# SwitchEthernet_-_Rev_A4.net
KiCad netlist of a schematic drawn in EAGLE
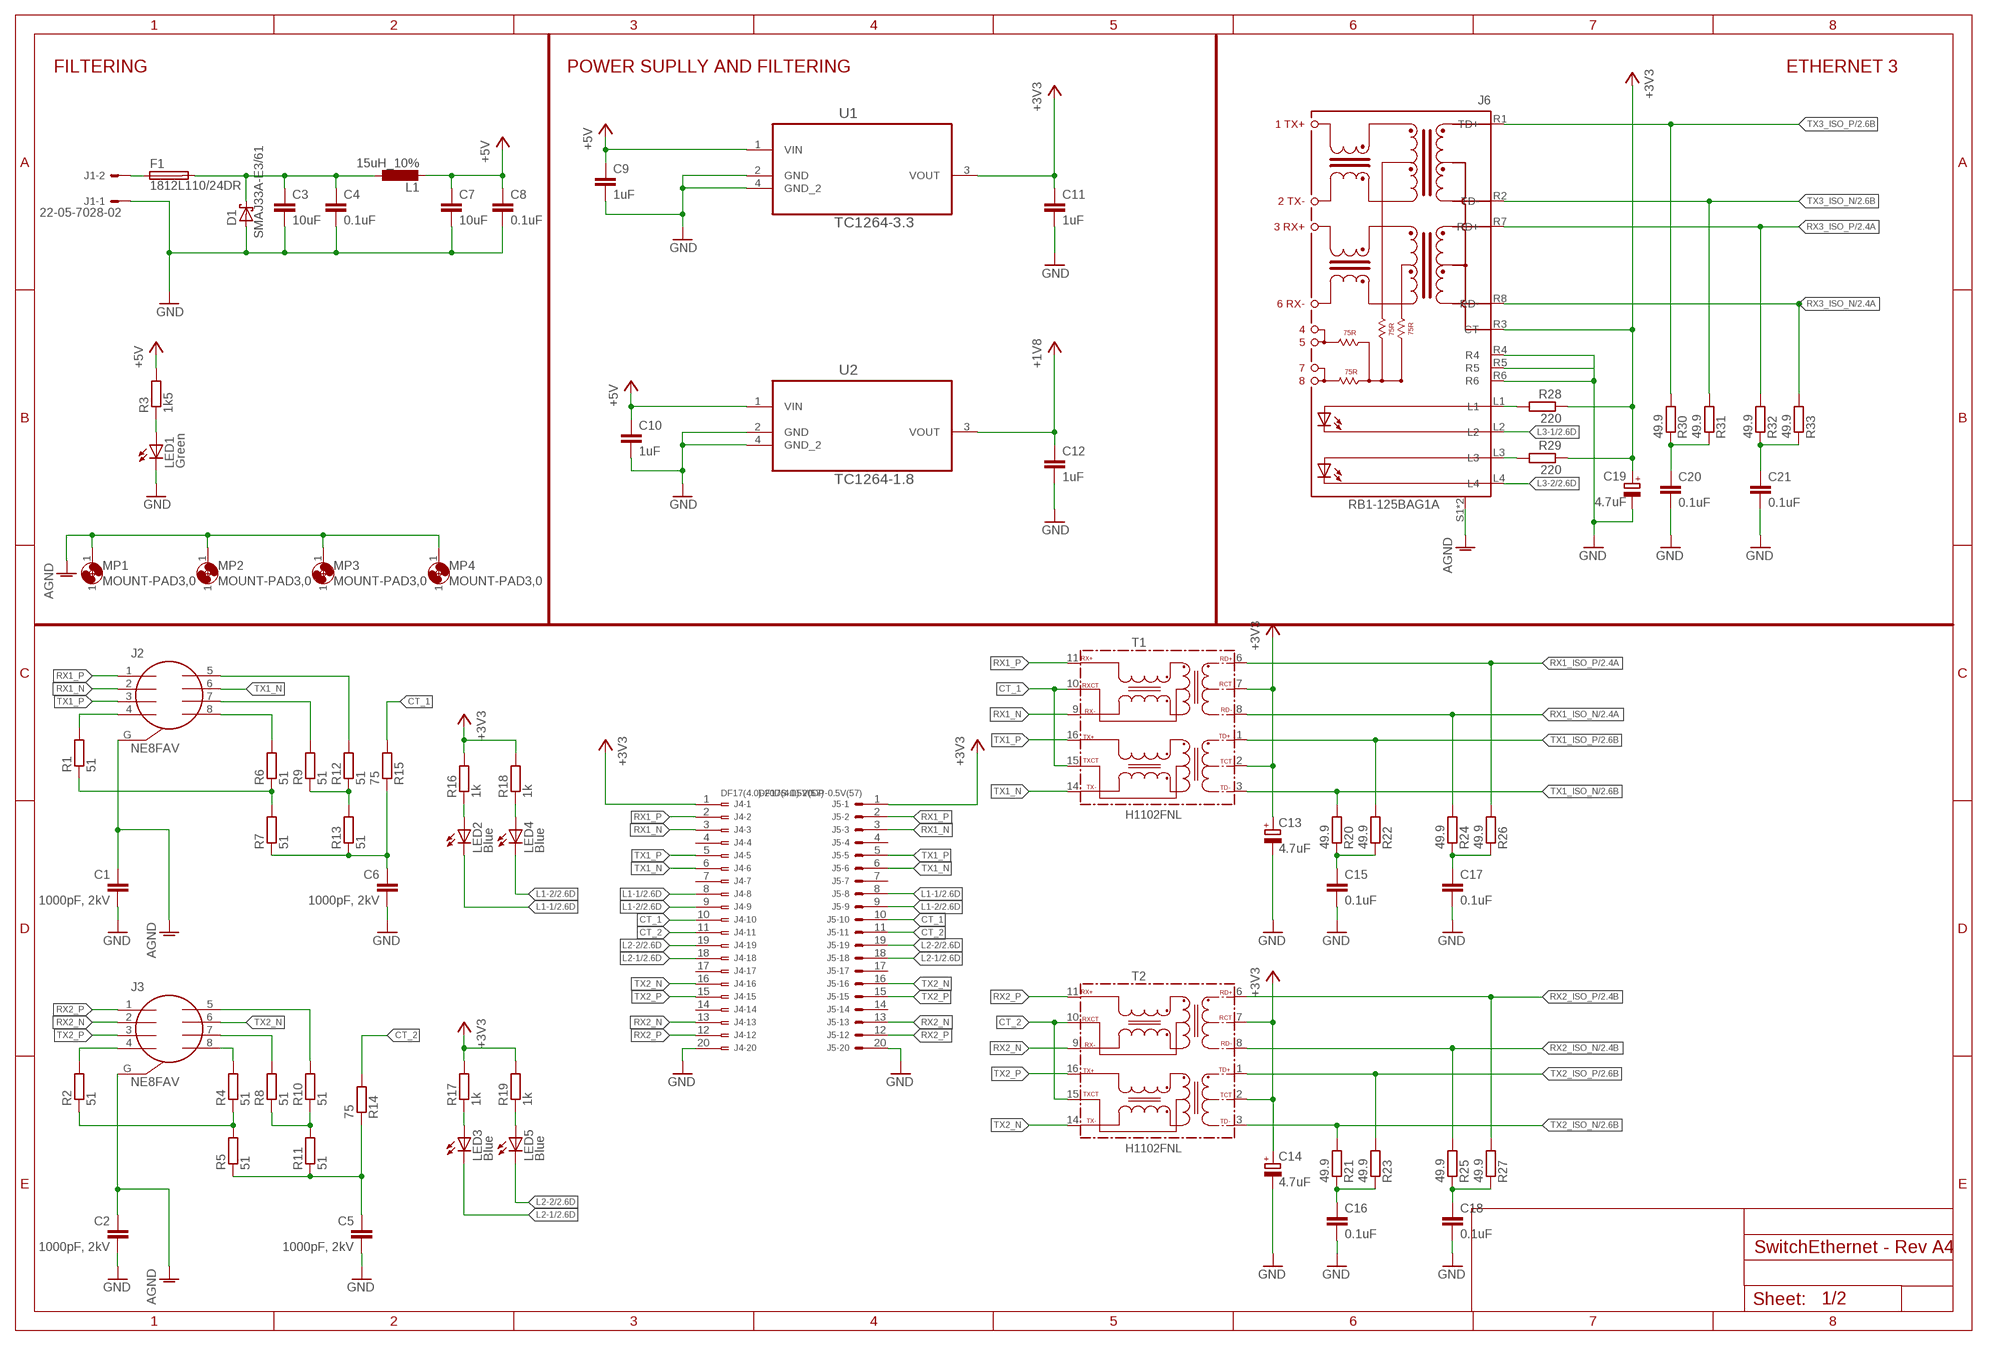
[diagram p0: schematic, sheet 1]
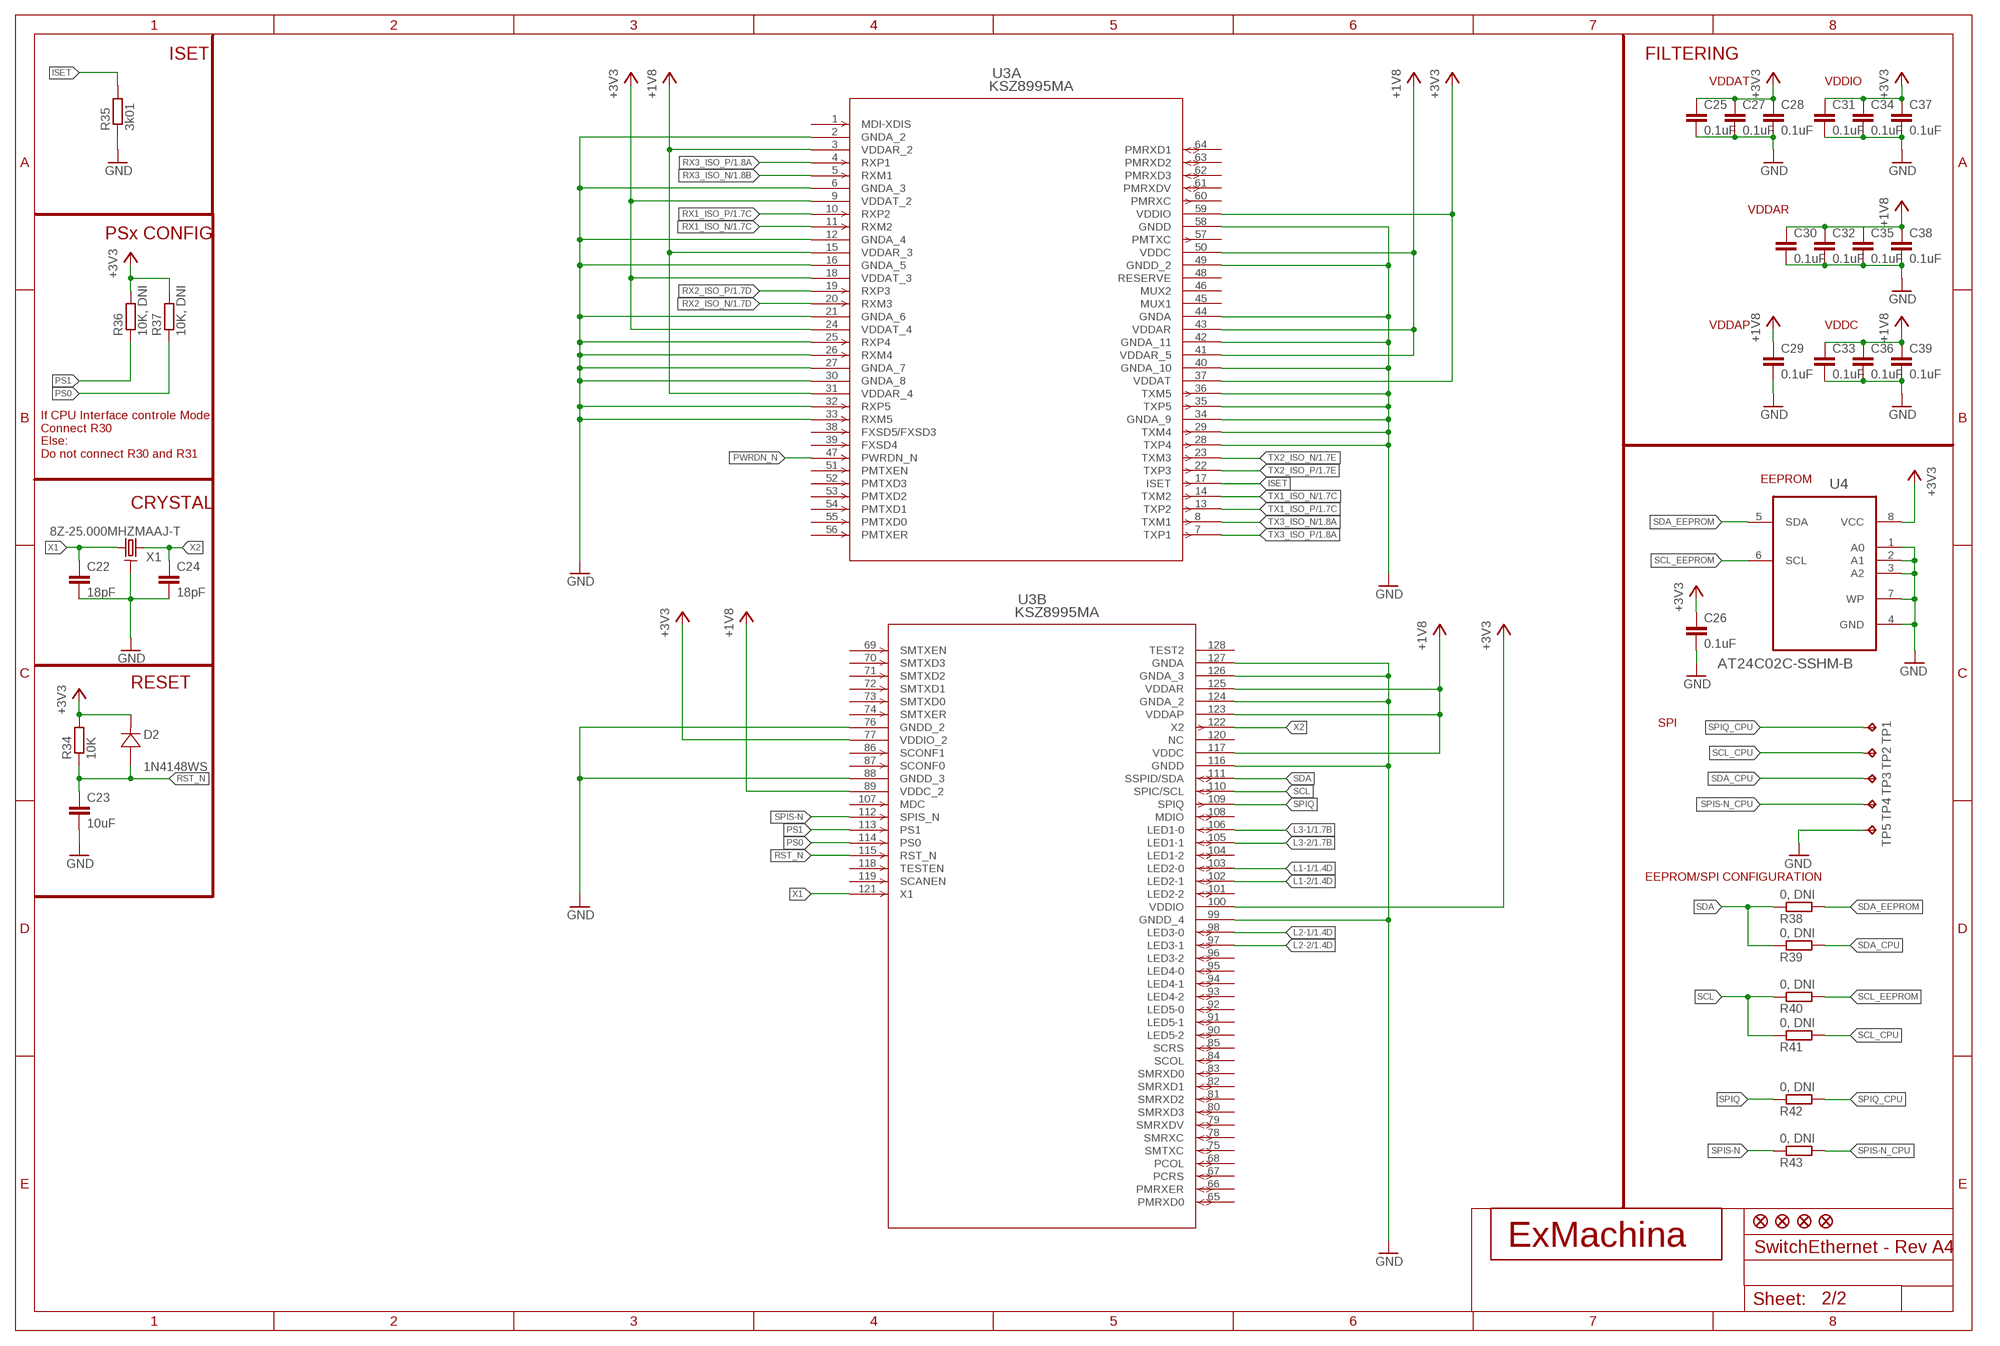
[diagram p1: schematic, sheet 2]

(export (version "E")
  (design (tool "Eeschema 10.0.6"))
  (components
    (comp (ref "C1")
      (value "1000pF, 2kV")
      (footprint "eagle-import:C1206")
      (fields (field (name "MPN") "MC1206B102K202CT"))
      (libsource (lib "eagle-import") (part "C-EUC1206"))
    )
    (comp (ref "C2")
      (value "1000pF, 2kV")
      (footprint "eagle-import:C1206")
      (fields (field (name "MPN") "MC1206B102K202CT"))
      (libsource (lib "eagle-import") (part "C-EUC1206"))
    )
    (comp (ref "C3")
      (value "10uF")
      (footprint "eagle-import:C0603")
      (fields (field (name "MPN") "GRM188R60J106ME47D"))
      (libsource (lib "eagle-import") (part "C-EUC0603"))
    )
    (comp (ref "C4")
      (value "0.1uF")
      (footprint "eagle-import:C0603")
      (fields (field (name "MPN") "MC0603B104K160CT"))
      (libsource (lib "eagle-import") (part "C-EUC0603"))
    )
    (comp (ref "C5")
      (value "1000pF, 2kV")
      (footprint "eagle-import:C1206")
      (fields (field (name "MPN") "MC1206B102K202CT"))
      (libsource (lib "eagle-import") (part "C-EUC1206"))
    )
    (comp (ref "C6")
      (value "1000pF, 2kV")
      (footprint "eagle-import:C1206")
      (fields (field (name "MPN") "MC1206B102K202CT"))
      (libsource (lib "eagle-import") (part "C-EUC1206"))
    )
    (comp (ref "C7")
      (value "10uF")
      (footprint "eagle-import:C0603")
      (fields (field (name "MPN") "GRM188R60J106ME47D"))
      (libsource (lib "eagle-import") (part "C-EUC0603"))
    )
    (comp (ref "C8")
      (value "0.1uF")
      (footprint "eagle-import:C0603")
      (fields (field (name "MPN") "MC0603B104K160CT"))
      (libsource (lib "eagle-import") (part "C-EUC0603"))
    )
    (comp (ref "C9")
      (value "1uF")
      (footprint "eagle-import:C0603")
      (fields (field (name "MPN") "MC0603B105K160CT"))
      (libsource (lib "eagle-import") (part "C-EUC0603"))
    )
    (comp (ref "C10")
      (value "1uF")
      (footprint "eagle-import:C0603")
      (fields (field (name "MPN") "MC0603B105K160CT"))
      (libsource (lib "eagle-import") (part "C-EUC0603"))
    )
    (comp (ref "C11")
      (value "1uF")
      (footprint "eagle-import:C0603")
      (fields (field (name "MPN") "MC0603B105K160CT"))
      (libsource (lib "eagle-import") (part "C-EUC0603"))
    )
    (comp (ref "C12")
      (value "1uF")
      (footprint "eagle-import:C0603")
      (fields (field (name "MPN") "MC0603B105K160CT"))
      (libsource (lib "eagle-import") (part "C-EUC0603"))
    )
    (comp (ref "C13")
      (value "4.7uF")
      (footprint "eagle-import:CT3216")
      (fields (field (name "MPN") "MCCTA475M010"))
      (libsource (lib "eagle-import") (part "CPOL-EUCT3216"))
    )
    (comp (ref "C14")
      (value "4.7uF")
      (footprint "eagle-import:CT3216")
      (fields (field (name "MPN") "MCCTA475M010"))
      (libsource (lib "eagle-import") (part "CPOL-EUCT3216"))
    )
    (comp (ref "C15")
      (value "0.1uF")
      (footprint "eagle-import:C0603")
      (fields (field (name "MPN") "MC0603B104K160CT"))
      (libsource (lib "eagle-import") (part "C-EUC0603"))
    )
    (comp (ref "C16")
      (value "0.1uF")
      (footprint "eagle-import:C0603")
      (fields (field (name "MPN") "MC0603B104K160CT"))
      (libsource (lib "eagle-import") (part "C-EUC0603"))
    )
    (comp (ref "C17")
      (value "0.1uF")
      (footprint "eagle-import:C0603")
      (fields (field (name "MPN") "MC0603B104K160CT"))
      (libsource (lib "eagle-import") (part "C-EUC0603"))
    )
    (comp (ref "C18")
      (value "0.1uF")
      (footprint "eagle-import:C0603")
      (fields (field (name "MPN") "MC0603B104K160CT"))
      (libsource (lib "eagle-import") (part "C-EUC0603"))
    )
    (comp (ref "C19")
      (value "4.7uF")
      (footprint "eagle-import:CT3216")
      (fields (field (name "MPN") "MCCTA475M010"))
      (libsource (lib "eagle-import") (part "CPOL-EUCT3216"))
    )
    (comp (ref "C20")
      (value "0.1uF")
      (footprint "eagle-import:C0603")
      (fields (field (name "MPN") "MC0603B104K160CT"))
      (libsource (lib "eagle-import") (part "C-EUC0603"))
    )
    (comp (ref "C21")
      (value "0.1uF")
      (footprint "eagle-import:C0603")
      (fields (field (name "MPN") "MC0603B104K160CT"))
      (libsource (lib "eagle-import") (part "C-EUC0603"))
    )
    (comp (ref "D1")
      (value "SMAJ33A-E3/61")
      (footprint "eagle-import:DIODE_DO-214AC")
      (fields
        (field (name "RSPARTNUMBER") "7103462")
        (field (name "COPYRIGHT") "Copyright (C) 2015 Accelerated Designs. All rights reserved")
      )
      (libsource (lib "eagle-import") (part "SMAJ33A-E3/61"))
    )
    (comp (ref "F1")
      (value "1812L110/24DR")
      (footprint "eagle-import:LITTLEFUSE_SMD")
      (libsource (lib "eagle-import") (part "1812L110/24DR"))
    )
    (comp (ref "J1")
      (value "22-05-7028-02")
      (footprint "eagle-import:7395-02")
      (fields (field (name "MPN") "22-05-7028") (field (name "OC_NEWARK") "25M1728"))
      (libsource (lib "eagle-import") (part "22-?-0205-7028"))
    )
    (comp (ref "J2")
      (value "NE8FAV")
      (footprint "eagle-import:NE8FAV")
      (fields (field (name "MF") "NEUTRIK") (field (name "OC_FARNELL") "1202031"))
      (libsource (lib "eagle-import") (part "NE8FAV"))
    )
    (comp (ref "J3")
      (value "NE8FAV")
      (footprint "eagle-import:NE8FAV")
      (fields (field (name "MF") "NEUTRIK") (field (name "OC_FARNELL") "1202031"))
      (libsource (lib "eagle-import") (part "NE8FAV"))
    )
    (comp (ref "J4")
      (value "DF17(4.0)-20DS-0.5V(57)")
      (footprint "eagle-import:DF17-20DS")
      (fields (field (name "MPN") "DF17(4.0)-20DS-0.5V(57)") (field (name "OC_NEWARK") "69W0567"))
      (libsource (lib "eagle-import") (part "DF17(?)-20DS-0.5V(57)4.0"))
    )
    (comp (ref "J5")
      (value "DF17(4.0)-20DP-0.5V(57)")
      (footprint "eagle-import:DF17-20DP")
      (fields (field (name "MPN") "DF17(4.0)-20DP-0.5V(57)") (field (name "OC_NEWARK") "69W0566"))
      (libsource (lib "eagle-import") (part "DF17(?)-20DP-0.5V(57)4.0"))
    )
    (comp (ref "J6")
      (value "RB1-125BAG1A")
      (footprint "eagle-import:WIZNET_RB1-125BAG1A")
      (libsource (lib "eagle-import") (part "RB1-125BAG1A"))
    )
    (comp (ref "L1")
      (value "15uH_10%")
      (footprint "eagle-import:L4532M")
      (fields (field (name "MPN") "LQH43CN150K03L"))
      (libsource (lib "eagle-import") (part "L-EUL4532C"))
    )
    (comp (ref "LED1")
      (value "Green")
      (footprint "eagle-import:CHIP-LED0603")
      (fields (field (name "MPN") "OVS-0604"))
      (libsource (lib "eagle-import") (part "LEDCHIP-LED0603"))
    )
    (comp (ref "LED2")
      (value "Blue")
      (footprint "eagle-import:CHIP-LED0603")
      (fields (field (name "MPN") "OVS-0603"))
      (libsource (lib "eagle-import") (part "LEDCHIP-LED0603"))
    )
    (comp (ref "LED3")
      (value "Blue")
      (footprint "eagle-import:CHIP-LED0603")
      (fields (field (name "MPN") "OVS-0603"))
      (libsource (lib "eagle-import") (part "LEDCHIP-LED0603"))
    )
    (comp (ref "LED4")
      (value "Blue")
      (footprint "eagle-import:CHIP-LED0603")
      (fields (field (name "MPN") "OVS-0603"))
      (libsource (lib "eagle-import") (part "LEDCHIP-LED0603"))
    )
    (comp (ref "LED5")
      (value "Blue")
      (footprint "eagle-import:CHIP-LED0603")
      (fields (field (name "MPN") "OVS-0603"))
      (libsource (lib "eagle-import") (part "LEDCHIP-LED0603"))
    )
    (comp (ref "MP1")
      (value "MOUNT-PAD3,0")
      (footprint "eagle-import:P3,0")
      (libsource (lib "eagle-import") (part "MOUNT-PAD3,0"))
    )
    (comp (ref "MP2")
      (value "MOUNT-PAD3,0")
      (footprint "eagle-import:P3,0")
      (libsource (lib "eagle-import") (part "MOUNT-PAD3,0"))
    )
    (comp (ref "MP3")
      (value "MOUNT-PAD3,0")
      (footprint "eagle-import:P3,0")
      (libsource (lib "eagle-import") (part "MOUNT-PAD3,0"))
    )
    (comp (ref "MP4")
      (value "MOUNT-PAD3,0")
      (footprint "eagle-import:P3,0")
      (libsource (lib "eagle-import") (part "MOUNT-PAD3,0"))
    )
    (comp (ref "R1")
      (value "51")
      (footprint "eagle-import:R0603")
      (fields (field (name "MF") "Multicomp Passives") (field (name "MPN") "MC0063W0603151R"))
      (libsource (lib "eagle-import") (part "R-EU_R0603"))
    )
    (comp (ref "R2")
      (value "51")
      (footprint "eagle-import:R0603")
      (fields (field (name "MF") "Multicomp Passives") (field (name "MPN") "MC0063W0603151R"))
      (libsource (lib "eagle-import") (part "R-EU_R0603"))
    )
    (comp (ref "R3")
      (value "1k5")
      (footprint "eagle-import:R0603")
      (fields (field (name "MF") "Multicomp Passives") (field (name "MPN") "MC0063W060311K5"))
      (libsource (lib "eagle-import") (part "R-EU_R0603"))
    )
    (comp (ref "R4")
      (value "51")
      (footprint "eagle-import:R0603")
      (fields (field (name "MF") "Multicomp Passives") (field (name "MPN") "MC0063W0603151R"))
      (libsource (lib "eagle-import") (part "R-EU_R0603"))
    )
    (comp (ref "R5")
      (value "51")
      (footprint "eagle-import:R0603")
      (fields (field (name "MF") "Multicomp Passives") (field (name "MPN") "MC0063W0603151R"))
      (libsource (lib "eagle-import") (part "R-EU_R0603"))
    )
    (comp (ref "R6")
      (value "51")
      (footprint "eagle-import:R0603")
      (fields (field (name "MF") "Multicomp Passives") (field (name "MPN") "MC0063W0603151R"))
      (libsource (lib "eagle-import") (part "R-EU_R0603"))
    )
    (comp (ref "R7")
      (value "51")
      (footprint "eagle-import:R0603")
      (fields (field (name "MF") "Multicomp Passives") (field (name "MPN") "MC0063W0603151R"))
      (libsource (lib "eagle-import") (part "R-EU_R0603"))
    )
    (comp (ref "R8")
      (value "51")
      (footprint "eagle-import:R0603")
      (fields (field (name "MF") "Multicomp Passives") (field (name "MPN") "MC0063W0603151R"))
      (libsource (lib "eagle-import") (part "R-EU_R0603"))
    )
    (comp (ref "R9")
      (value "51")
      (footprint "eagle-import:R0603")
      (fields (field (name "MF") "Multicomp Passives") (field (name "MPN") "MC0063W0603151R"))
      (libsource (lib "eagle-import") (part "R-EU_R0603"))
    )
    (comp (ref "R10")
      (value "51")
      (footprint "eagle-import:R0603")
      (fields (field (name "MF") "Multicomp Passives") (field (name "MPN") "MC0063W0603151R"))
      (libsource (lib "eagle-import") (part "R-EU_R0603"))
    )
    (comp (ref "R11")
      (value "51")
      (footprint "eagle-import:R0603")
      (fields (field (name "MF") "Multicomp Passives") (field (name "MPN") "MC0063W0603151R"))
      (libsource (lib "eagle-import") (part "R-EU_R0603"))
    )
    (comp (ref "R12")
      (value "51")
      (footprint "eagle-import:R0603")
      (fields (field (name "MF") "Multicomp Passives") (field (name "MPN") "MC0063W0603151R"))
      (libsource (lib "eagle-import") (part "R-EU_R0603"))
    )
    (comp (ref "R13")
      (value "51")
      (footprint "eagle-import:R0603")
      (fields (field (name "MF") "Multicomp Passives") (field (name "MPN") "MC0063W0603151R"))
      (libsource (lib "eagle-import") (part "R-EU_R0603"))
    )
    (comp (ref "R14")
      (value "75")
      (footprint "eagle-import:R0603")
      (fields (field (name "MF") "Multicomp Passives") (field (name "MPN") "MC0063W0603175R"))
      (libsource (lib "eagle-import") (part "R-EU_R0603"))
    )
    (comp (ref "R15")
      (value "75")
      (footprint "eagle-import:R0603")
      (fields (field (name "MF") "Multicomp Passives") (field (name "MPN") "MC0063W0603175R"))
      (libsource (lib "eagle-import") (part "R-EU_R0603"))
    )
    (comp (ref "R16")
      (value "1k")
      (footprint "eagle-import:R0603")
      (fields (field (name "MPN") "MCMR06X1001FTL"))
      (libsource (lib "eagle-import") (part "R-EU_R0603"))
    )
    (comp (ref "R17")
      (value "1k")
      (footprint "eagle-import:R0603")
      (fields (field (name "MPN") "MCMR06X1001FTL"))
      (libsource (lib "eagle-import") (part "R-EU_R0603"))
    )
    (comp (ref "R18")
      (value "1k")
      (footprint "eagle-import:R0603")
      (fields (field (name "MPN") "MCMR06X1001FTL"))
      (libsource (lib "eagle-import") (part "R-EU_R0603"))
    )
    (comp (ref "R19")
      (value "1k")
      (footprint "eagle-import:R0603")
      (fields (field (name "MPN") "MCMR06X1001FTL"))
      (libsource (lib "eagle-import") (part "R-EU_R0603"))
    )
    (comp (ref "R20")
      (value "49.9")
      (footprint "eagle-import:R0603")
      (fields (field (name "MPN") "MC0603SAF499JT5E"))
      (libsource (lib "eagle-import") (part "R-EU_R0603"))
    )
    (comp (ref "R21")
      (value "49.9")
      (footprint "eagle-import:R0603")
      (fields (field (name "MPN") "MC0603SAF499JT5E"))
      (libsource (lib "eagle-import") (part "R-EU_R0603"))
    )
    (comp (ref "R22")
      (value "49.9")
      (footprint "eagle-import:R0603")
      (fields (field (name "MPN") "MC0603SAF499JT5E"))
      (libsource (lib "eagle-import") (part "R-EU_R0603"))
    )
    (comp (ref "R23")
      (value "49.9")
      (footprint "eagle-import:R0603")
      (fields (field (name "MPN") "MC0603SAF499JT5E"))
      (libsource (lib "eagle-import") (part "R-EU_R0603"))
    )
    (comp (ref "R24")
      (value "49.9")
      (footprint "eagle-import:R0603")
      (fields (field (name "MPN") "MC0603SAF499JT5E"))
      (libsource (lib "eagle-import") (part "R-EU_R0603"))
    )
    (comp (ref "R25")
      (value "49.9")
      (footprint "eagle-import:R0603")
      (fields (field (name "MPN") "MC0603SAF499JT5E"))
      (libsource (lib "eagle-import") (part "R-EU_R0603"))
    )
    (comp (ref "R26")
      (value "49.9")
      (footprint "eagle-import:R0603")
      (fields (field (name "MPN") "MC0603SAF499JT5E"))
      (libsource (lib "eagle-import") (part "R-EU_R0603"))
    )
    (comp (ref "R27")
      (value "49.9")
      (footprint "eagle-import:R0603")
      (fields (field (name "MPN") "MC0603SAF499JT5E"))
      (libsource (lib "eagle-import") (part "R-EU_R0603"))
    )
    (comp (ref "R28")
      (value "220")
      (footprint "eagle-import:R0603")
      (fields (field (name "MF") "Multicomp Passives") (field (name "MPN") "MC0063W06031220R"))
      (libsource (lib "eagle-import") (part "R-EU_R0603"))
    )
    (comp (ref "R29")
      (value "220")
      (footprint "eagle-import:R0603")
      (fields (field (name "MF") "Multicomp Passives") (field (name "MPN") "MC0063W06031220R"))
      (libsource (lib "eagle-import") (part "R-EU_R0603"))
    )
    (comp (ref "R30")
      (value "49.9")
      (footprint "eagle-import:R0603")
      (fields (field (name "MPN") "MC0603SAF499JT5E"))
      (libsource (lib "eagle-import") (part "R-EU_R0603"))
    )
    (comp (ref "R31")
      (value "49.9")
      (footprint "eagle-import:R0603")
      (fields (field (name "MPN") "MC0603SAF499JT5E"))
      (libsource (lib "eagle-import") (part "R-EU_R0603"))
    )
    (comp (ref "R32")
      (value "49.9")
      (footprint "eagle-import:R0603")
      (fields (field (name "MPN") "MC0603SAF499JT5E"))
      (libsource (lib "eagle-import") (part "R-EU_R0603"))
    )
    (comp (ref "R33")
      (value "49.9")
      (footprint "eagle-import:R0603")
      (fields (field (name "MPN") "MC0603SAF499JT5E"))
      (libsource (lib "eagle-import") (part "R-EU_R0603"))
    )
    (comp (ref "T1")
      (value "H1102FNL")
      (footprint "eagle-import:HXXXX")
      (libsource (lib "eagle-import") (part "H1102FNL"))
    )
    (comp (ref "T2")
      (value "H1102FNL")
      (footprint "eagle-import:HXXXX")
      (libsource (lib "eagle-import") (part "H1102FNL"))
    )
    (comp (ref "U1")
      (value "TC1264-3.3")
      (footprint "eagle-import:SOT230P700X180-4N")
      (fields (field (name "MF") "MICROCHIP") (field (name "MPN") "TC1264-3.3VDB"))
      (libsource (lib "eagle-import") (part "TC1264-3.3"))
    )
    (comp (ref "U2")
      (value "TC1264-1.8")
      (footprint "eagle-import:SOT230P700X180-4N")
      (fields (field (name "MF") "MICROCHIP") (field (name "MPN") "TC1264-1.8VDBTR"))
      (libsource (lib "eagle-import") (part "TC1264-1.8"))
    )
    (comp (ref "C22")
      (value "18pF")
      (footprint "eagle-import:C0603")
      (fields (field (name "MPN") "MC0603N180J500CT"))
      (libsource (lib "eagle-import") (part "C-EUC0603"))
    )
    (comp (ref "C23")
      (value "10uF")
      (footprint "eagle-import:C0603")
      (fields (field (name "MPN") "GRM188R60J106ME47D"))
      (libsource (lib "eagle-import") (part "C-EUC0603"))
    )
    (comp (ref "C24")
      (value "18pF")
      (footprint "eagle-import:C0603")
      (fields (field (name "MPN") "MC0603N180J500CT"))
      (libsource (lib "eagle-import") (part "C-EUC0603"))
    )
    (comp (ref "C25")
      (value "0.1uF")
      (footprint "eagle-import:C0603")
      (fields (field (name "MPN") "MC0603B104K160CT"))
      (libsource (lib "eagle-import") (part "C-EUC0603"))
    )
    (comp (ref "C26")
      (value "0.1uF")
      (footprint "eagle-import:C0603")
      (fields (field (name "MPN") "MC0603B104K160CT"))
      (libsource (lib "eagle-import") (part "C-EUC0603"))
    )
    (comp (ref "C27")
      (value "0.1uF")
      (footprint "eagle-import:C0603")
      (fields (field (name "MPN") "MC0603B104K160CT"))
      (libsource (lib "eagle-import") (part "C-EUC0603"))
    )
    (comp (ref "C28")
      (value "0.1uF")
      (footprint "eagle-import:C0603")
      (fields (field (name "MPN") "MC0603B104K160CT"))
      (libsource (lib "eagle-import") (part "C-EUC0603"))
    )
    (comp (ref "C29")
      (value "0.1uF")
      (footprint "eagle-import:C0603")
      (fields (field (name "MPN") "MC0603B104K160CT"))
      (libsource (lib "eagle-import") (part "C-EUC0603"))
    )
    (comp (ref "C30")
      (value "0.1uF")
      (footprint "eagle-import:C0603")
      (fields (field (name "MPN") "MC0603B104K160CT"))
      (libsource (lib "eagle-import") (part "C-EUC0603"))
    )
    (comp (ref "C31")
      (value "0.1uF")
      (footprint "eagle-import:C0603")
      (fields (field (name "MPN") "MC0603B104K160CT"))
      (libsource (lib "eagle-import") (part "C-EUC0603"))
    )
    (comp (ref "C32")
      (value "0.1uF")
      (footprint "eagle-import:C0603")
      (fields (field (name "MPN") "MC0603B104K160CT"))
      (libsource (lib "eagle-import") (part "C-EUC0603"))
    )
    (comp (ref "C33")
      (value "0.1uF")
      (footprint "eagle-import:C0603")
      (fields (field (name "MPN") "MC0603B104K160CT"))
      (libsource (lib "eagle-import") (part "C-EUC0603"))
    )
    (comp (ref "C34")
      (value "0.1uF")
      (footprint "eagle-import:C0603")
      (fields (field (name "MPN") "MC0603B104K160CT"))
      (libsource (lib "eagle-import") (part "C-EUC0603"))
    )
    (comp (ref "C35")
      (value "0.1uF")
      (footprint "eagle-import:C0603")
      (fields (field (name "MPN") "MC0603B104K160CT"))
      (libsource (lib "eagle-import") (part "C-EUC0603"))
    )
    (comp (ref "C36")
      (value "0.1uF")
      (footprint "eagle-import:C0603")
      (fields (field (name "MPN") "MC0603B104K160CT"))
      (libsource (lib "eagle-import") (part "C-EUC0603"))
    )
    (comp (ref "C37")
      (value "0.1uF")
      (footprint "eagle-import:C0603")
      (fields (field (name "MPN") "MC0603B104K160CT"))
      (libsource (lib "eagle-import") (part "C-EUC0603"))
    )
    (comp (ref "C38")
      (value "0.1uF")
      (footprint "eagle-import:C0603")
      (fields (field (name "MPN") "MC0603B104K160CT"))
      (libsource (lib "eagle-import") (part "C-EUC0603"))
    )
    (comp (ref "C39")
      (value "0.1uF")
      (footprint "eagle-import:C0603")
      (fields (field (name "MPN") "MC0603B104K160CT"))
      (libsource (lib "eagle-import") (part "C-EUC0603"))
    )
    (comp (ref "D2")
      (value "1N4148WS")
      (footprint "eagle-import:SOD323-W")
      (fields (field (name "MPN") "1N4148WS."))
      (libsource (lib "eagle-import") (part "1N4148WS"))
    )
    (comp (ref "JP1")
      (value "FIDUCIAL1X2")
      (footprint "eagle-import:FIDUCIAL-1X2")
      (libsource (lib "eagle-import") (part "FIDUCIAL1X2"))
    )
    (comp (ref "JP2")
      (value "FIDUCIAL1X2")
      (footprint "eagle-import:FIDUCIAL-1X2")
      (libsource (lib "eagle-import") (part "FIDUCIAL1X2"))
    )
    (comp (ref "JP3")
      (value "FIDUCIAL1X2")
      (footprint "eagle-import:FIDUCIAL-1X2")
      (libsource (lib "eagle-import") (part "FIDUCIAL1X2"))
    )
    (comp (ref "JP4")
      (value "FIDUCIAL1X2")
      (footprint "eagle-import:FIDUCIAL-1X2")
      (libsource (lib "eagle-import") (part "FIDUCIAL1X2"))
    )
    (comp (ref "R34")
      (value "10K")
      (footprint "eagle-import:R0603")
      (fields (field (name "MF") "Multicomp Passives") (field (name "MPN") "MC0063W0603110K"))
      (libsource (lib "eagle-import") (part "R-EU_R0603"))
    )
    (comp (ref "R35")
      (value "3k01")
      (footprint "eagle-import:R0603")
      (fields (field (name "MPN") "MC0063W060313K01"))
      (libsource (lib "eagle-import") (part "R-EU_R0603"))
    )
    (comp (ref "R36")
      (value "10K, DNI")
      (footprint "eagle-import:R0603")
      (fields (field (name "MF") "Multicomp Passives") (field (name "MPN") "MC0063W0603110K"))
      (libsource (lib "eagle-import") (part "R-EU_R0603"))
    )
    (comp (ref "R37")
      (value "10K, DNI")
      (footprint "eagle-import:R0603")
      (fields (field (name "MF") "Multicomp Passives") (field (name "MPN") "MC0063W0603110K"))
      (libsource (lib "eagle-import") (part "R-EU_R0603"))
    )
    (comp (ref "R38")
      (value "0, DNI")
      (footprint "eagle-import:R0603")
      (fields (field (name "MF") "Multicomp Passives") (field (name "MPN") "MC0603WG00000T5E-TC"))
      (libsource (lib "eagle-import") (part "R-EU_R0603"))
    )
    (comp (ref "R39")
      (value "0, DNI")
      (footprint "eagle-import:R0603")
      (fields (field (name "MF") "Multicomp Passives") (field (name "MPN") "MC0603WG00000T5E-TC"))
      (libsource (lib "eagle-import") (part "R-EU_R0603"))
    )
    (comp (ref "R40")
      (value "0, DNI")
      (footprint "eagle-import:R0603")
      (fields (field (name "MF") "Multicomp Passives") (field (name "MPN") "MC0603WG00000T5E-TC"))
      (libsource (lib "eagle-import") (part "R-EU_R0603"))
    )
    (comp (ref "R41")
      (value "0, DNI")
      (footprint "eagle-import:R0603")
      (fields (field (name "MF") "Multicomp Passives") (field (name "MPN") "MC0603WG00000T5E-TC"))
      (libsource (lib "eagle-import") (part "R-EU_R0603"))
    )
    (comp (ref "R42")
      (value "0, DNI")
      (footprint "eagle-import:R0603")
      (fields (field (name "MF") "Multicomp Passives") (field (name "MPN") "MC0603WG00000T5E-TC"))
      (libsource (lib "eagle-import") (part "R-EU_R0603"))
    )
    (comp (ref "R43")
      (value "0, DNI")
      (footprint "eagle-import:R0603")
      (fields (field (name "MF") "Multicomp Passives") (field (name "MPN") "MC0603WG00000T5E-TC"))
      (libsource (lib "eagle-import") (part "R-EU_R0603"))
    )
    (comp (ref "T3")
      (value "EXMACHINA-LOGO-NAME")
      (footprint "eagle-import:EXM-LOGO-BASELINE")
      (libsource (lib "eagle-import") (part "EXMACHINA-LOGO-NAME"))
    )
    (comp (ref "TP1")
      (value "TPB1,27")
      (footprint "eagle-import:B1,27")
      (libsource (lib "eagle-import") (part "TPB1,27"))
    )
    (comp (ref "TP2")
      (value "TPB1,27")
      (footprint "eagle-import:B1,27")
      (libsource (lib "eagle-import") (part "TPB1,27"))
    )
    (comp (ref "TP3")
      (value "TPB1,27")
      (footprint "eagle-import:B1,27")
      (libsource (lib "eagle-import") (part "TPB1,27"))
    )
    (comp (ref "TP4")
      (value "TPB1,27")
      (footprint "eagle-import:B1,27")
      (libsource (lib "eagle-import") (part "TPB1,27"))
    )
    (comp (ref "TP5")
      (value "TPB1,27")
      (footprint "eagle-import:B1,27")
      (libsource (lib "eagle-import") (part "TPB1,27"))
    )
    (comp (ref "U3")
      (value "KSZ8995MA")
      (footprint "eagle-import:PQFP-128_MQL")
      (fields
        (field (name "MANUFACTURER_PART_NUMBER") "ksz8995ma")
        (field (name "OC_FARNELL") "2509844")
        (field (name "OC_NEWARK") "unknown")
        (field (name "COPYRIGHT") "Copyright (C) 2015 Accelerated Designs. All rights reserved")
      )
      (libsource (lib "eagle-import") (part "KSZ8995MA"))
    )
    (comp (ref "U4")
      (value "AT24C02C-SSHM-B")
      (footprint "eagle-import:SOIC127P600X175-8N")
      (fields (field (name "OC_FARNELL") "1971995"))
      (libsource (lib "eagle-import") (part "AT24C02C-SSHM-B"))
    )
    (comp (ref "X1")
      (value "8Z-25.000MHZMAAJ-T")
      (footprint "eagle-import:SMD2.5X2")
      (fields (field (name "MPN") "8Z-25.000MAAJ-T"))
      (libsource (lib "eagle-import") (part "8Z-25.000MHZMAAJ-T"))
    )
  )
  (nets
    (net (code "1") (name "+1V8") (class "Default")
      (node (ref "C12") (pin "1") (pinfunction "1_1") (pintype "passive"))
      (node (ref "C29") (pin "1") (pinfunction "1_1") (pintype "passive"))
      (node (ref "C30") (pin "1") (pinfunction "1_1") (pintype "passive"))
      (node (ref "C32") (pin "1") (pinfunction "1_1") (pintype "passive"))
      (node (ref "C33") (pin "1") (pinfunction "1_1") (pintype "passive"))
      (node (ref "C35") (pin "1") (pinfunction "1_1") (pintype "passive"))
      (node (ref "C36") (pin "1") (pinfunction "1_1") (pintype "passive"))
      (node (ref "C38") (pin "1") (pinfunction "1_1") (pintype "passive"))
      (node (ref "C39") (pin "1") (pinfunction "1_1") (pintype "passive"))
      (node (ref "U2") (pin "3") (pinfunction "VOUT_3") (pintype "output"))
      (node (ref "U3") (pin "117") (pinfunction "VDDC_117") (pintype "power_in"))
      (node (ref "U3") (pin "123") (pinfunction "VDDAP_123") (pintype "power_in"))
      (node (ref "U3") (pin "125") (pinfunction "VDDAR_125") (pintype "power_in"))
      (node (ref "U3") (pin "15") (pinfunction "VDDAR_3_15") (pintype "power_in"))
      (node (ref "U3") (pin "3") (pinfunction "VDDAR_2_3") (pintype "power_in"))
      (node (ref "U3") (pin "31") (pinfunction "VDDAR_4_31") (pintype "power_in"))
      (node (ref "U3") (pin "41") (pinfunction "VDDAR_5_41") (pintype "power_in"))
      (node (ref "U3") (pin "43") (pinfunction "VDDAR_43") (pintype "power_in"))
      (node (ref "U3") (pin "50") (pinfunction "VDDC_50") (pintype "power_in"))
      (node (ref "U3") (pin "89") (pinfunction "VDDC_2_89") (pintype "power_in"))
    )
    (net (code "2") (name "+3V3") (class "Default")
      (node (ref "C11") (pin "1") (pinfunction "1_1") (pintype "passive"))
      (node (ref "C13") (pin "+") (pinfunction "+_+") (pintype "passive"))
      (node (ref "C14") (pin "+") (pinfunction "+_+") (pintype "passive"))
      (node (ref "C19") (pin "+") (pinfunction "+_+") (pintype "passive"))
      (node (ref "C25") (pin "1") (pinfunction "1_1") (pintype "passive"))
      (node (ref "C26") (pin "1") (pinfunction "1_1") (pintype "passive"))
      (node (ref "C27") (pin "1") (pinfunction "1_1") (pintype "passive"))
      (node (ref "C28") (pin "1") (pinfunction "1_1") (pintype "passive"))
      (node (ref "C31") (pin "1") (pinfunction "1_1") (pintype "passive"))
      (node (ref "C34") (pin "1") (pinfunction "1_1") (pintype "passive"))
      (node (ref "C37") (pin "1") (pinfunction "1_1") (pintype "passive"))
      (node (ref "D2") (pin "C") (pinfunction "1_C") (pintype "passive"))
      (node (ref "J4") (pin "1") (pinfunction "P_1") (pintype "bidirectional"))
      (node (ref "J5") (pin "1") (pinfunction "P_1") (pintype "bidirectional"))
      (node (ref "J6") (pin "R3") (pinfunction "CT_R3") (pintype "input"))
      (node (ref "R16") (pin "2") (pinfunction "2_2") (pintype "passive"))
      (node (ref "R17") (pin "2") (pinfunction "2_2") (pintype "passive"))
      (node (ref "R18") (pin "2") (pinfunction "2_2") (pintype "passive"))
      (node (ref "R19") (pin "2") (pinfunction "2_2") (pintype "passive"))
      (node (ref "R28") (pin "1") (pinfunction "1_1") (pintype "passive"))
      (node (ref "R29") (pin "1") (pinfunction "1_1") (pintype "passive"))
      (node (ref "R34") (pin "2") (pinfunction "2_2") (pintype "passive"))
      (node (ref "R36") (pin "2") (pinfunction "2_2") (pintype "passive"))
      (node (ref "R37") (pin "2") (pinfunction "2_2") (pintype "passive"))
      (node (ref "T1") (pin "2") (pinfunction "TCT_2") (pintype "bidirectional"))
      (node (ref "T1") (pin "7") (pinfunction "RCT_7") (pintype "bidirectional"))
      (node (ref "T2") (pin "2") (pinfunction "TCT_2") (pintype "bidirectional"))
      (node (ref "T2") (pin "7") (pinfunction "RCT_7") (pintype "bidirectional"))
      (node (ref "U1") (pin "3") (pinfunction "VOUT_3") (pintype "output"))
      (node (ref "U3") (pin "100") (pinfunction "VDDIO_100") (pintype "power_in"))
      (node (ref "U3") (pin "18") (pinfunction "VDDAT_3_18") (pintype "power_in"))
      (node (ref "U3") (pin "24") (pinfunction "VDDAT_4_24") (pintype "power_in"))
      (node (ref "U3") (pin "37") (pinfunction "VDDAT_37") (pintype "power_in"))
      (node (ref "U3") (pin "59") (pinfunction "VDDIO_59") (pintype "power_in"))
      (node (ref "U3") (pin "77") (pinfunction "VDDIO_2_77") (pintype "power_in"))
      (node (ref "U3") (pin "9") (pinfunction "VDDAT_2_9") (pintype "power_in"))
      (node (ref "U4") (pin "8") (pinfunction "VCC_8") (pintype "power_in"))
    )
    (net (code "3") (name "+5V") (class "Default")
      (node (ref "C10") (pin "1") (pinfunction "1_1") (pintype "passive"))
      (node (ref "C7") (pin "1") (pinfunction "1_1") (pintype "passive"))
      (node (ref "C8") (pin "1") (pinfunction "1_1") (pintype "passive"))
      (node (ref "C9") (pin "1") (pinfunction "1_1") (pintype "passive"))
      (node (ref "L1") (pin "2") (pinfunction "2_2") (pintype "passive"))
      (node (ref "R3") (pin "2") (pinfunction "2_2") (pintype "passive"))
      (node (ref "U1") (pin "1") (pinfunction "VIN_1") (pintype "input"))
      (node (ref "U2") (pin "1") (pinfunction "VIN_1") (pintype "input"))
    )
    (net (code "4") (name "AGND") (class "Default")
      (node (ref "C1") (pin "1") (pinfunction "1_1") (pintype "passive"))
      (node (ref "C2") (pin "1") (pinfunction "1_1") (pintype "passive"))
      (node (ref "J2") (pin "G") (pinfunction "G_G") (pintype "passive"))
      (node (ref "J3") (pin "G") (pinfunction "G_G") (pintype "passive"))
      (node (ref "J6") (pin "S1") (pinfunction "P$1_S1") (pintype "bidirectional"))
      (node (ref "J6") (pin "S2") (pinfunction "P$1_S2") (pintype "bidirectional"))
      (node (ref "MP1") (pin "1") (pinfunction "1_1") (pintype "power_in"))
      (node (ref "MP2") (pin "1") (pinfunction "1_1") (pintype "power_in"))
      (node (ref "MP3") (pin "1") (pinfunction "1_1") (pintype "power_in"))
      (node (ref "MP4") (pin "1") (pinfunction "1_1") (pintype "power_in"))
    )
    (net (code "5") (name "CT_1") (class "Default")
      (node (ref "J4") (pin "10") (pinfunction "P_10") (pintype "bidirectional"))
      (node (ref "J5") (pin "10") (pinfunction "P_10") (pintype "bidirectional"))
      (node (ref "R15") (pin "2") (pinfunction "2_2") (pintype "passive"))
      (node (ref "T1") (pin "10") (pinfunction "RXCT_10") (pintype "bidirectional"))
      (node (ref "T1") (pin "15") (pinfunction "TXCT_15") (pintype "bidirectional"))
    )
    (net (code "6") (name "CT_2") (class "Default")
      (node (ref "J4") (pin "11") (pinfunction "P_11") (pintype "bidirectional"))
      (node (ref "J5") (pin "11") (pinfunction "P_11") (pintype "bidirectional"))
      (node (ref "R14") (pin "2") (pinfunction "2_2") (pintype "passive"))
      (node (ref "T2") (pin "10") (pinfunction "RXCT_10") (pintype "bidirectional"))
      (node (ref "T2") (pin "15") (pinfunction "TXCT_15") (pintype "bidirectional"))
    )
    (net (code "7") (name "GND") (class "Default")
      (node (ref "C1") (pin "2") (pinfunction "2_2") (pintype "passive"))
      (node (ref "C10") (pin "2") (pinfunction "2_2") (pintype "passive"))
      (node (ref "C11") (pin "2") (pinfunction "2_2") (pintype "passive"))
      (node (ref "C12") (pin "2") (pinfunction "2_2") (pintype "passive"))
      (node (ref "C13") (pin "-") (pinfunction "-_-") (pintype "passive"))
      (node (ref "C14") (pin "-") (pinfunction "-_-") (pintype "passive"))
      (node (ref "C15") (pin "2") (pinfunction "2_2") (pintype "passive"))
      (node (ref "C16") (pin "2") (pinfunction "2_2") (pintype "passive"))
      (node (ref "C17") (pin "2") (pinfunction "2_2") (pintype "passive"))
      (node (ref "C18") (pin "2") (pinfunction "2_2") (pintype "passive"))
      (node (ref "C19") (pin "-") (pinfunction "-_-") (pintype "passive"))
      (node (ref "C2") (pin "2") (pinfunction "2_2") (pintype "passive"))
      (node (ref "C20") (pin "2") (pinfunction "2_2") (pintype "passive"))
      (node (ref "C21") (pin "2") (pinfunction "2_2") (pintype "passive"))
      (node (ref "C22") (pin "2") (pinfunction "2_2") (pintype "passive"))
      (node (ref "C23") (pin "2") (pinfunction "2_2") (pintype "passive"))
      (node (ref "C24") (pin "2") (pinfunction "2_2") (pintype "passive"))
      (node (ref "C25") (pin "2") (pinfunction "2_2") (pintype "passive"))
      (node (ref "C26") (pin "2") (pinfunction "2_2") (pintype "passive"))
      (node (ref "C27") (pin "2") (pinfunction "2_2") (pintype "passive"))
      (node (ref "C28") (pin "2") (pinfunction "2_2") (pintype "passive"))
      (node (ref "C29") (pin "2") (pinfunction "2_2") (pintype "passive"))
      (node (ref "C3") (pin "2") (pinfunction "2_2") (pintype "passive"))
      (node (ref "C30") (pin "2") (pinfunction "2_2") (pintype "passive"))
      (node (ref "C31") (pin "2") (pinfunction "2_2") (pintype "passive"))
      (node (ref "C32") (pin "2") (pinfunction "2_2") (pintype "passive"))
      (node (ref "C33") (pin "2") (pinfunction "2_2") (pintype "passive"))
      (node (ref "C34") (pin "2") (pinfunction "2_2") (pintype "passive"))
      (node (ref "C35") (pin "2") (pinfunction "2_2") (pintype "passive"))
      (node (ref "C36") (pin "2") (pinfunction "2_2") (pintype "passive"))
      (node (ref "C37") (pin "2") (pinfunction "2_2") (pintype "passive"))
      (node (ref "C38") (pin "2") (pinfunction "2_2") (pintype "passive"))
      (node (ref "C39") (pin "2") (pinfunction "2_2") (pintype "passive"))
      (node (ref "C4") (pin "2") (pinfunction "2_2") (pintype "passive"))
      (node (ref "C5") (pin "2") (pinfunction "2_2") (pintype "passive"))
      (node (ref "C6") (pin "2") (pinfunction "2_2") (pintype "passive"))
      (node (ref "C7") (pin "2") (pinfunction "2_2") (pintype "passive"))
      (node (ref "C8") (pin "2") (pinfunction "2_2") (pintype "passive"))
      (node (ref "C9") (pin "2") (pinfunction "2_2") (pintype "passive"))
      (node (ref "D1") (pin "2") (pinfunction "A_2") (pintype "passive"))
      (node (ref "J1") (pin "1") (pinfunction "S_1") (pintype "passive"))
      (node (ref "J4") (pin "20") (pinfunction "P_20") (pintype "bidirectional"))
      (node (ref "J5") (pin "20") (pinfunction "P_20") (pintype "bidirectional"))
      (node (ref "J6") (pin "R4") (pinfunction "R4_R4") (pintype "input"))
      (node (ref "J6") (pin "R5") (pinfunction "R5_R5") (pintype "input"))
      (node (ref "J6") (pin "R6") (pinfunction "R6_R6") (pintype "input"))
      (node (ref "LED1") (pin "C") (pinfunction "C_C") (pintype "passive"))
      (node (ref "R35") (pin "1") (pinfunction "1_1") (pintype "passive"))
      (node (ref "TP5") (pin "TP") (pinfunction "TP_TP") (pintype "input"))
      (node (ref "U1") (pin "2") (pinfunction "GND_2") (pintype "passive"))
      (node (ref "U1") (pin "4") (pinfunction "GND_2_4") (pintype "passive"))
      (node (ref "U2") (pin "2") (pinfunction "GND_2") (pintype "passive"))
      (node (ref "U2") (pin "4") (pinfunction "GND_2_4") (pintype "passive"))
      (node (ref "U3") (pin "116") (pinfunction "GNDD_116") (pintype "power_in"))
      (node (ref "U3") (pin "12") (pinfunction "GNDA_4_12") (pintype "power_in"))
      (node (ref "U3") (pin "124") (pinfunction "GNDA_2_124") (pintype "power_in"))
      (node (ref "U3") (pin "126") (pinfunction "GNDA_3_126") (pintype "power_in"))
      (node (ref "U3") (pin "127") (pinfunction "GNDA_127") (pintype "power_in"))
      (node (ref "U3") (pin "16") (pinfunction "GNDA_5_16") (pintype "power_in"))
      (node (ref "U3") (pin "2") (pinfunction "GNDA_2_2") (pintype "power_in"))
      (node (ref "U3") (pin "21") (pinfunction "GNDA_6_21") (pintype "power_in"))
      (node (ref "U3") (pin "25") (pinfunction "RXP4_25") (pintype "input"))
      (node (ref "U3") (pin "26") (pinfunction "RXM4_26") (pintype "input"))
      (node (ref "U3") (pin "27") (pinfunction "GNDA_7_27") (pintype "power_in"))
      (node (ref "U3") (pin "28") (pinfunction "TXP4_28") (pintype "output"))
      (node (ref "U3") (pin "29") (pinfunction "TXM4_29") (pintype "output"))
      (node (ref "U3") (pin "30") (pinfunction "GNDA_8_30") (pintype "power_in"))
      (node (ref "U3") (pin "32") (pinfunction "RXP5_32") (pintype "input"))
      (node (ref "U3") (pin "33") (pinfunction "RXM5_33") (pintype "input"))
      (node (ref "U3") (pin "34") (pinfunction "GNDA_9_34") (pintype "power_in"))
      (node (ref "U3") (pin "35") (pinfunction "TXP5_35") (pintype "output"))
      (node (ref "U3") (pin "36") (pinfunction "TXM5_36") (pintype "output"))
      (node (ref "U3") (pin "40") (pinfunction "GNDA_10_40") (pintype "power_in"))
      (node (ref "U3") (pin "42") (pinfunction "GNDA_11_42") (pintype "power_in"))
      (node (ref "U3") (pin "44") (pinfunction "GNDA_44") (pintype "power_in"))
      (node (ref "U3") (pin "49") (pinfunction "GNDD_2_49") (pintype "passive"))
      (node (ref "U3") (pin "58") (pinfunction "GNDD_58") (pintype "power_in"))
      (node (ref "U3") (pin "6") (pinfunction "GNDA_3_6") (pintype "power_in"))
      (node (ref "U3") (pin "76") (pinfunction "GNDD_2_76") (pintype "power_in"))
      (node (ref "U3") (pin "88") (pinfunction "GNDD_3_88") (pintype "power_in"))
      (node (ref "U3") (pin "99") (pinfunction "GNDD_4_99") (pintype "power_in"))
      (node (ref "U4") (pin "1") (pinfunction "A0_1") (pintype "input"))
      (node (ref "U4") (pin "2") (pinfunction "A1_2") (pintype "input"))
      (node (ref "U4") (pin "3") (pinfunction "A2_3") (pintype "input"))
      (node (ref "U4") (pin "4") (pinfunction "GND_4") (pintype "power_in"))
      (node (ref "U4") (pin "7") (pinfunction "WP_7") (pintype "input"))
      (node (ref "X1") (pin "2") (pinfunction "2_2") (pintype "passive"))
      (node (ref "X1") (pin "4") (pinfunction "2_4") (pintype "passive"))
    )
    (net (code "8") (name "ISET") (class "Default")
      (node (ref "R35") (pin "2") (pinfunction "2_2") (pintype "passive"))
      (node (ref "U3") (pin "17") (pinfunction "ISET_17") (pintype "output"))
    )
    (net (code "9") (name "L1-1") (class "Default")
      (node (ref "J4") (pin "8") (pinfunction "P_8") (pintype "bidirectional"))
      (node (ref "J5") (pin "8") (pinfunction "P_8") (pintype "bidirectional"))
      (node (ref "LED2") (pin "C") (pinfunction "C_C") (pintype "passive"))
      (node (ref "U3") (pin "103") (pinfunction "LED2-0_103") (pintype "bidirectional"))
    )
    (net (code "10") (name "L1-2") (class "Default")
      (node (ref "J4") (pin "9") (pinfunction "P_9") (pintype "bidirectional"))
      (node (ref "J5") (pin "9") (pinfunction "P_9") (pintype "bidirectional"))
      (node (ref "LED4") (pin "C") (pinfunction "C_C") (pintype "passive"))
      (node (ref "U3") (pin "102") (pinfunction "LED2-1_102") (pintype "bidirectional"))
    )
    (net (code "11") (name "L2-1") (class "Default")
      (node (ref "J4") (pin "18") (pinfunction "P_18") (pintype "bidirectional"))
      (node (ref "J5") (pin "18") (pinfunction "P_18") (pintype "bidirectional"))
      (node (ref "LED3") (pin "C") (pinfunction "C_C") (pintype "passive"))
      (node (ref "U3") (pin "98") (pinfunction "LED3-0_98") (pintype "bidirectional"))
    )
    (net (code "12") (name "L2-2") (class "Default")
      (node (ref "J4") (pin "19") (pinfunction "P_19") (pintype "bidirectional"))
      (node (ref "J5") (pin "19") (pinfunction "P_19") (pintype "bidirectional"))
      (node (ref "LED5") (pin "C") (pinfunction "C_C") (pintype "passive"))
      (node (ref "U3") (pin "97") (pinfunction "LED3-1_97") (pintype "bidirectional"))
    )
    (net (code "13") (name "L3-1") (class "Default")
      (node (ref "J6") (pin "L2") (pinfunction "L2_L2") (pintype "passive"))
      (node (ref "U3") (pin "106") (pinfunction "LED1-0_106") (pintype "bidirectional"))
    )
    (net (code "14") (name "L3-2") (class "Default")
      (node (ref "J6") (pin "L4") (pinfunction "L4_L4") (pintype "passive"))
      (node (ref "U3") (pin "105") (pinfunction "LED1-1_105") (pintype "bidirectional"))
    )
    (net (code "15") (name "Net-(C5-Pad1)") (class "Default")
      (node (ref "C5") (pin "1") (pinfunction "1_1") (pintype "passive"))
      (node (ref "R11") (pin "1") (pinfunction "1_1") (pintype "passive"))
      (node (ref "R14") (pin "1") (pinfunction "1_1") (pintype "passive"))
      (node (ref "R5") (pin "1") (pinfunction "1_1") (pintype "passive"))
    )
    (net (code "16") (name "Net-(C6-Pad1)") (class "Default")
      (node (ref "C6") (pin "1") (pinfunction "1_1") (pintype "passive"))
      (node (ref "R13") (pin "1") (pinfunction "1_1") (pintype "passive"))
      (node (ref "R15") (pin "1") (pinfunction "1_1") (pintype "passive"))
      (node (ref "R7") (pin "1") (pinfunction "1_1") (pintype "passive"))
    )
    (net (code "17") (name "Net-(C15-Pad1)") (class "Default")
      (node (ref "C15") (pin "1") (pinfunction "1_1") (pintype "passive"))
      (node (ref "R20") (pin "1") (pinfunction "1_1") (pintype "passive"))
      (node (ref "R22") (pin "1") (pinfunction "1_1") (pintype "passive"))
    )
    (net (code "18") (name "Net-(C16-Pad1)") (class "Default")
      (node (ref "C16") (pin "1") (pinfunction "1_1") (pintype "passive"))
      (node (ref "R21") (pin "1") (pinfunction "1_1") (pintype "passive"))
      (node (ref "R23") (pin "1") (pinfunction "1_1") (pintype "passive"))
    )
    (net (code "19") (name "Net-(C17-Pad1)") (class "Default")
      (node (ref "C17") (pin "1") (pinfunction "1_1") (pintype "passive"))
      (node (ref "R24") (pin "1") (pinfunction "1_1") (pintype "passive"))
      (node (ref "R26") (pin "1") (pinfunction "1_1") (pintype "passive"))
    )
    (net (code "20") (name "Net-(C18-Pad1)") (class "Default")
      (node (ref "C18") (pin "1") (pinfunction "1_1") (pintype "passive"))
      (node (ref "R25") (pin "1") (pinfunction "1_1") (pintype "passive"))
      (node (ref "R27") (pin "1") (pinfunction "1_1") (pintype "passive"))
    )
    (net (code "21") (name "Net-(C20-Pad1)") (class "Default")
      (node (ref "C20") (pin "1") (pinfunction "1_1") (pintype "passive"))
      (node (ref "R30") (pin "1") (pinfunction "1_1") (pintype "passive"))
      (node (ref "R31") (pin "1") (pinfunction "1_1") (pintype "passive"))
    )
    (net (code "22") (name "Net-(C21-Pad1)") (class "Default")
      (node (ref "C21") (pin "1") (pinfunction "1_1") (pintype "passive"))
      (node (ref "R32") (pin "1") (pinfunction "1_1") (pintype "passive"))
      (node (ref "R33") (pin "1") (pinfunction "1_1") (pintype "passive"))
    )
    (net (code "23") (name "Net-(D1-C)") (class "Default")
      (node (ref "C3") (pin "1") (pinfunction "1_1") (pintype "passive"))
      (node (ref "C4") (pin "1") (pinfunction "1_1") (pintype "passive"))
      (node (ref "D1") (pin "1") (pinfunction "C_1") (pintype "passive"))
      (node (ref "F1") (pin "2") (pinfunction "2_2") (pintype "passive"))
      (node (ref "L1") (pin "1") (pinfunction "1_1") (pintype "passive"))
    )
    (net (code "24") (name "Net-(J1B-S)") (class "Default")
      (node (ref "F1") (pin "1") (pinfunction "1_1") (pintype "passive"))
      (node (ref "J1") (pin "2") (pinfunction "S_2") (pintype "passive"))
    )
    (net (code "25") (name "Net-(J2-Pad4)") (class "Default")
      (node (ref "J2") (pin "4") (pinfunction "4_4") (pintype "passive"))
      (node (ref "R1") (pin "2") (pinfunction "2_2") (pintype "passive"))
    )
    (net (code "26") (name "Net-(J2-Pad5)") (class "Default")
      (node (ref "J2") (pin "5") (pinfunction "5_5") (pintype "passive"))
      (node (ref "R12") (pin "2") (pinfunction "2_2") (pintype "passive"))
    )
    (net (code "27") (name "Net-(J2-Pad7)") (class "Default")
      (node (ref "J2") (pin "7") (pinfunction "7_7") (pintype "passive"))
      (node (ref "R9") (pin "2") (pinfunction "2_2") (pintype "passive"))
    )
    (net (code "28") (name "Net-(J2-Pad8)") (class "Default")
      (node (ref "J2") (pin "8") (pinfunction "8_8") (pintype "passive"))
      (node (ref "R6") (pin "2") (pinfunction "2_2") (pintype "passive"))
    )
    (net (code "29") (name "Net-(J3-Pad4)") (class "Default")
      (node (ref "J3") (pin "4") (pinfunction "4_4") (pintype "passive"))
      (node (ref "R2") (pin "2") (pinfunction "2_2") (pintype "passive"))
    )
    (net (code "30") (name "Net-(J3-Pad5)") (class "Default")
      (node (ref "J3") (pin "5") (pinfunction "5_5") (pintype "passive"))
      (node (ref "R10") (pin "2") (pinfunction "2_2") (pintype "passive"))
    )
    (net (code "31") (name "Net-(J3-Pad7)") (class "Default")
      (node (ref "J3") (pin "7") (pinfunction "7_7") (pintype "passive"))
      (node (ref "R8") (pin "2") (pinfunction "2_2") (pintype "passive"))
    )
    (net (code "32") (name "Net-(J3-Pad8)") (class "Default")
      (node (ref "J3") (pin "8") (pinfunction "8_8") (pintype "passive"))
      (node (ref "R4") (pin "2") (pinfunction "2_2") (pintype "passive"))
    )
    (net (code "33") (name "Net-(J6-PadL1)") (class "Default")
      (node (ref "J6") (pin "L1") (pinfunction "L1_L1") (pintype "passive"))
      (node (ref "R28") (pin "2") (pinfunction "2_2") (pintype "passive"))
    )
    (net (code "34") (name "Net-(J6-PadL3)") (class "Default")
      (node (ref "J6") (pin "L3") (pinfunction "L3_L3") (pintype "passive"))
      (node (ref "R29") (pin "2") (pinfunction "2_2") (pintype "passive"))
    )
    (net (code "35") (name "Net-(LED1-PadA)") (class "Default")
      (node (ref "LED1") (pin "A") (pinfunction "A_A") (pintype "passive"))
      (node (ref "R3") (pin "1") (pinfunction "1_1") (pintype "passive"))
    )
    (net (code "36") (name "Net-(LED2-PadA)") (class "Default")
      (node (ref "LED2") (pin "A") (pinfunction "A_A") (pintype "passive"))
      (node (ref "R16") (pin "1") (pinfunction "1_1") (pintype "passive"))
    )
    (net (code "37") (name "Net-(LED3-PadA)") (class "Default")
      (node (ref "LED3") (pin "A") (pinfunction "A_A") (pintype "passive"))
      (node (ref "R17") (pin "1") (pinfunction "1_1") (pintype "passive"))
    )
    (net (code "38") (name "Net-(LED4-PadA)") (class "Default")
      (node (ref "LED4") (pin "A") (pinfunction "A_A") (pintype "passive"))
      (node (ref "R18") (pin "1") (pinfunction "1_1") (pintype "passive"))
    )
    (net (code "39") (name "Net-(LED5-PadA)") (class "Default")
      (node (ref "LED5") (pin "A") (pinfunction "A_A") (pintype "passive"))
      (node (ref "R19") (pin "1") (pinfunction "1_1") (pintype "passive"))
    )
    (net (code "40") (name "Net-(R1-Pad1)") (class "Default")
      (node (ref "R1") (pin "1") (pinfunction "1_1") (pintype "passive"))
      (node (ref "R6") (pin "1") (pinfunction "1_1") (pintype "passive"))
      (node (ref "R7") (pin "2") (pinfunction "2_2") (pintype "passive"))
    )
    (net (code "41") (name "Net-(R2-Pad1)") (class "Default")
      (node (ref "R2") (pin "1") (pinfunction "1_1") (pintype "passive"))
      (node (ref "R4") (pin "1") (pinfunction "1_1") (pintype "passive"))
      (node (ref "R5") (pin "2") (pinfunction "2_2") (pintype "passive"))
    )
    (net (code "42") (name "Net-(R10-Pad1)") (class "Default")
      (node (ref "R10") (pin "1") (pinfunction "1_1") (pintype "passive"))
      (node (ref "R11") (pin "2") (pinfunction "2_2") (pintype "passive"))
      (node (ref "R8") (pin "1") (pinfunction "1_1") (pintype "passive"))
    )
    (net (code "43") (name "Net-(R12-Pad1)") (class "Default")
      (node (ref "R12") (pin "1") (pinfunction "1_1") (pintype "passive"))
      (node (ref "R13") (pin "2") (pinfunction "2_2") (pintype "passive"))
      (node (ref "R9") (pin "1") (pinfunction "1_1") (pintype "passive"))
    )
    (net (code "44") (name "PS0") (class "Default")
      (node (ref "R37") (pin "1") (pinfunction "1_1") (pintype "passive"))
      (node (ref "U3") (pin "114") (pinfunction "PS0_114") (pintype "input"))
    )
    (net (code "45") (name "PS1") (class "Default")
      (node (ref "R36") (pin "1") (pinfunction "1_1") (pintype "passive"))
      (node (ref "U3") (pin "113") (pinfunction "PS1_113") (pintype "input"))
    )
    (net (code "46") (name "PWRDN_N") (class "Default")
      (node (ref "U3") (pin "47") (pinfunction "PWRDN_N_47") (pintype "input"))
    )
    (net (code "47") (name "RST_N") (class "Default")
      (node (ref "C23") (pin "1") (pinfunction "1_1") (pintype "passive"))
      (node (ref "D2") (pin "A") (pinfunction "2_A") (pintype "passive"))
      (node (ref "R34") (pin "1") (pinfunction "1_1") (pintype "passive"))
      (node (ref "U3") (pin "115") (pinfunction "RST_N_115") (pintype "input"))
    )
    (net (code "48") (name "RX1_ISO_N") (class "Default")
      (node (ref "R24") (pin "2") (pinfunction "2_2") (pintype "passive"))
      (node (ref "T1") (pin "8") (pinfunction "RD-_8") (pintype "bidirectional"))
      (node (ref "U3") (pin "11") (pinfunction "RXM2_11") (pintype "input"))
    )
    (net (code "49") (name "RX1_ISO_P") (class "Default")
      (node (ref "R26") (pin "2") (pinfunction "2_2") (pintype "passive"))
      (node (ref "T1") (pin "6") (pinfunction "RD+_6") (pintype "bidirectional"))
      (node (ref "U3") (pin "10") (pinfunction "RXP2_10") (pintype "input"))
    )
    (net (code "50") (name "RX1_N") (class "Default")
      (node (ref "J2") (pin "2") (pinfunction "2_2") (pintype "passive"))
      (node (ref "J4") (pin "3") (pinfunction "P_3") (pintype "bidirectional"))
      (node (ref "J5") (pin "3") (pinfunction "P_3") (pintype "bidirectional"))
      (node (ref "T1") (pin "9") (pinfunction "RX-_9") (pintype "bidirectional"))
    )
    (net (code "51") (name "RX1_P") (class "Default")
      (node (ref "J2") (pin "1") (pinfunction "1_1") (pintype "passive"))
      (node (ref "J4") (pin "2") (pinfunction "P_2") (pintype "bidirectional"))
      (node (ref "J5") (pin "2") (pinfunction "P_2") (pintype "bidirectional"))
      (node (ref "T1") (pin "11") (pinfunction "RX+_11") (pintype "bidirectional"))
    )
    (net (code "52") (name "RX2_ISO_N") (class "Default")
      (node (ref "R25") (pin "2") (pinfunction "2_2") (pintype "passive"))
      (node (ref "T2") (pin "8") (pinfunction "RD-_8") (pintype "bidirectional"))
      (node (ref "U3") (pin "20") (pinfunction "RXM3_20") (pintype "input"))
    )
    (net (code "53") (name "RX2_ISO_P") (class "Default")
      (node (ref "R27") (pin "2") (pinfunction "2_2") (pintype "passive"))
      (node (ref "T2") (pin "6") (pinfunction "RD+_6") (pintype "bidirectional"))
      (node (ref "U3") (pin "19") (pinfunction "RXP3_19") (pintype "input"))
    )
    (net (code "54") (name "RX2_N") (class "Default")
      (node (ref "J3") (pin "2") (pinfunction "2_2") (pintype "passive"))
      (node (ref "J4") (pin "13") (pinfunction "P_13") (pintype "bidirectional"))
      (node (ref "J5") (pin "13") (pinfunction "P_13") (pintype "bidirectional"))
      (node (ref "T2") (pin "9") (pinfunction "RX-_9") (pintype "bidirectional"))
    )
    (net (code "55") (name "RX2_P") (class "Default")
      (node (ref "J3") (pin "1") (pinfunction "1_1") (pintype "passive"))
      (node (ref "J4") (pin "12") (pinfunction "P_12") (pintype "bidirectional"))
      (node (ref "J5") (pin "12") (pinfunction "P_12") (pintype "bidirectional"))
      (node (ref "T2") (pin "11") (pinfunction "RX+_11") (pintype "bidirectional"))
    )
    (net (code "56") (name "RX3_ISO_N") (class "Default")
      (node (ref "J6") (pin "R8") (pinfunction "RD-_R8") (pintype "input"))
      (node (ref "R33") (pin "2") (pinfunction "2_2") (pintype "passive"))
      (node (ref "U3") (pin "5") (pinfunction "RXM1_5") (pintype "input"))
    )
    (net (code "57") (name "RX3_ISO_P") (class "Default")
      (node (ref "J6") (pin "R7") (pinfunction "RD+_R7") (pintype "input"))
      (node (ref "R32") (pin "2") (pinfunction "2_2") (pintype "passive"))
      (node (ref "U3") (pin "4") (pinfunction "RXP1_4") (pintype "input"))
    )
    (net (code "58") (name "SCL") (class "Default")
      (node (ref "R40") (pin "1") (pinfunction "1_1") (pintype "passive"))
      (node (ref "R41") (pin "1") (pinfunction "1_1") (pintype "passive"))
      (node (ref "U3") (pin "110") (pinfunction "SPIC/SCL_110") (pintype "bidirectional"))
    )
    (net (code "59") (name "SCL_CPU") (class "Default")
      (node (ref "R41") (pin "2") (pinfunction "2_2") (pintype "passive"))
      (node (ref "TP2") (pin "TP") (pinfunction "TP_TP") (pintype "input"))
    )
    (net (code "60") (name "SCL_EEPROM") (class "Default")
      (node (ref "R40") (pin "2") (pinfunction "2_2") (pintype "passive"))
      (node (ref "U4") (pin "6") (pinfunction "SCL_6") (pintype "input"))
    )
    (net (code "61") (name "SDA") (class "Default")
      (node (ref "R38") (pin "1") (pinfunction "1_1") (pintype "passive"))
      (node (ref "R39") (pin "1") (pinfunction "1_1") (pintype "passive"))
      (node (ref "U3") (pin "111") (pinfunction "SSPID/SDA_111") (pintype "bidirectional"))
    )
    (net (code "62") (name "SDA_CPU") (class "Default")
      (node (ref "R39") (pin "2") (pinfunction "2_2") (pintype "passive"))
      (node (ref "TP3") (pin "TP") (pinfunction "TP_TP") (pintype "input"))
    )
    (net (code "63") (name "SDA_EEPROM") (class "Default")
      (node (ref "R38") (pin "2") (pinfunction "2_2") (pintype "passive"))
      (node (ref "U4") (pin "5") (pinfunction "SDA_5") (pintype "bidirectional"))
    )
    (net (code "64") (name "SPIQ") (class "Default")
      (node (ref "R42") (pin "1") (pinfunction "1_1") (pintype "passive"))
      (node (ref "U3") (pin "109") (pinfunction "SPIQ_109") (pintype "output"))
    )
    (net (code "65") (name "SPIQ_CPU") (class "Default")
      (node (ref "R42") (pin "2") (pinfunction "2_2") (pintype "passive"))
      (node (ref "TP1") (pin "TP") (pinfunction "TP_TP") (pintype "input"))
    )
    (net (code "66") (name "SPIS-N") (class "Default")
      (node (ref "R43") (pin "1") (pinfunction "1_1") (pintype "passive"))
      (node (ref "U3") (pin "112") (pinfunction "SPIS_N_112") (pintype "input"))
    )
    (net (code "67") (name "SPIS-N_CPU") (class "Default")
      (node (ref "R43") (pin "2") (pinfunction "2_2") (pintype "passive"))
      (node (ref "TP4") (pin "TP") (pinfunction "TP_TP") (pintype "input"))
    )
    (net (code "68") (name "TX1_ISO_N") (class "Default")
      (node (ref "R20") (pin "2") (pinfunction "2_2") (pintype "passive"))
      (node (ref "T1") (pin "3") (pinfunction "TD-_3") (pintype "bidirectional"))
      (node (ref "U3") (pin "14") (pinfunction "TXM2_14") (pintype "output"))
    )
    (net (code "69") (name "TX1_ISO_P") (class "Default")
      (node (ref "R22") (pin "2") (pinfunction "2_2") (pintype "passive"))
      (node (ref "T1") (pin "1") (pinfunction "TD+_1") (pintype "bidirectional"))
      (node (ref "U3") (pin "13") (pinfunction "TXP2_13") (pintype "output"))
    )
    (net (code "70") (name "TX1_N") (class "Default")
      (node (ref "J2") (pin "6") (pinfunction "6_6") (pintype "passive"))
      (node (ref "J4") (pin "6") (pinfunction "P_6") (pintype "bidirectional"))
      (node (ref "J5") (pin "6") (pinfunction "P_6") (pintype "bidirectional"))
      (node (ref "T1") (pin "14") (pinfunction "TX-_14") (pintype "bidirectional"))
    )
    (net (code "71") (name "TX1_P") (class "Default")
      (node (ref "J2") (pin "3") (pinfunction "3_3") (pintype "passive"))
      (node (ref "J4") (pin "5") (pinfunction "P_5") (pintype "bidirectional"))
      (node (ref "J5") (pin "5") (pinfunction "P_5") (pintype "bidirectional"))
      (node (ref "T1") (pin "16") (pinfunction "TX+_16") (pintype "bidirectional"))
    )
    (net (code "72") (name "TX2_ISO_N") (class "Default")
      (node (ref "R21") (pin "2") (pinfunction "2_2") (pintype "passive"))
      (node (ref "T2") (pin "3") (pinfunction "TD-_3") (pintype "bidirectional"))
      (node (ref "U3") (pin "23") (pinfunction "TXM3_23") (pintype "output"))
    )
    (net (code "73") (name "TX2_ISO_P") (class "Default")
      (node (ref "R23") (pin "2") (pinfunction "2_2") (pintype "passive"))
      (node (ref "T2") (pin "1") (pinfunction "TD+_1") (pintype "bidirectional"))
      (node (ref "U3") (pin "22") (pinfunction "TXP3_22") (pintype "output"))
    )
    (net (code "74") (name "TX2_N") (class "Default")
      (node (ref "J3") (pin "6") (pinfunction "6_6") (pintype "passive"))
      (node (ref "J4") (pin "16") (pinfunction "P_16") (pintype "bidirectional"))
      (node (ref "J5") (pin "16") (pinfunction "P_16") (pintype "bidirectional"))
      (node (ref "T2") (pin "14") (pinfunction "TX-_14") (pintype "bidirectional"))
    )
    (net (code "75") (name "TX2_P") (class "Default")
      (node (ref "J3") (pin "3") (pinfunction "3_3") (pintype "passive"))
      (node (ref "J4") (pin "15") (pinfunction "P_15") (pintype "bidirectional"))
      (node (ref "J5") (pin "15") (pinfunction "P_15") (pintype "bidirectional"))
      (node (ref "T2") (pin "16") (pinfunction "TX+_16") (pintype "bidirectional"))
    )
    (net (code "76") (name "TX3_ISO_N") (class "Default")
      (node (ref "J6") (pin "R2") (pinfunction "TD-_R2") (pintype "input"))
      (node (ref "R31") (pin "2") (pinfunction "2_2") (pintype "passive"))
      (node (ref "U3") (pin "8") (pinfunction "TXM1_8") (pintype "output"))
    )
    (net (code "77") (name "TX3_ISO_P") (class "Default")
      (node (ref "J6") (pin "R1") (pinfunction "TD+_R1") (pintype "input"))
      (node (ref "R30") (pin "2") (pinfunction "2_2") (pintype "passive"))
      (node (ref "U3") (pin "7") (pinfunction "TXP1_7") (pintype "output"))
    )
    (net (code "78") (name "X1") (class "Default")
      (node (ref "C22") (pin "1") (pinfunction "1_1") (pintype "passive"))
      (node (ref "U3") (pin "121") (pinfunction "X1_121") (pintype "input"))
      (node (ref "X1") (pin "1") (pinfunction "1_1") (pintype "passive"))
    )
    (net (code "79") (name "X2") (class "Default")
      (node (ref "C24") (pin "1") (pinfunction "1_1") (pintype "passive"))
      (node (ref "U3") (pin "122") (pinfunction "X2_122") (pintype "output"))
      (node (ref "X1") (pin "3") (pinfunction "3_3") (pintype "passive"))
    )
    (net (code "80") (name "unconnected-(J4F-P-Pad14)") (class "Default")
      (node (ref "J4") (pin "14") (pinfunction "P_14") (pintype "bidirectional"))
    )
    (net (code "81") (name "unconnected-(J4I-P-Pad17)") (class "Default")
      (node (ref "J4") (pin "17") (pinfunction "P_17") (pintype "bidirectional"))
    )
    (net (code "82") (name "unconnected-(J4O-P-Pad4)") (class "Default")
      (node (ref "J4") (pin "4") (pinfunction "P_4") (pintype "bidirectional"))
    )
    (net (code "83") (name "unconnected-(J4R-P-Pad7)") (class "Default")
      (node (ref "J4") (pin "7") (pinfunction "P_7") (pintype "bidirectional"))
    )
    (net (code "84") (name "unconnected-(J5F-P-Pad14)") (class "Default")
      (node (ref "J5") (pin "14") (pinfunction "P_14") (pintype "bidirectional"))
    )
    (net (code "85") (name "unconnected-(J5I-P-Pad17)") (class "Default")
      (node (ref "J5") (pin "17") (pinfunction "P_17") (pintype "bidirectional"))
    )
    (net (code "86") (name "unconnected-(J5O-P-Pad4)") (class "Default")
      (node (ref "J5") (pin "4") (pinfunction "P_4") (pintype "bidirectional"))
    )
    (net (code "87") (name "unconnected-(J5R-P-Pad7)") (class "Default")
      (node (ref "J5") (pin "7") (pinfunction "P_7") (pintype "bidirectional"))
    )
    (net (code "88") (name "unconnected-(U3A-FXSD4-Pad39)") (class "Default")
      (node (ref "U3") (pin "39") (pinfunction "FXSD4_39") (pintype "input"))
    )
    (net (code "89") (name "unconnected-(U3A-FXSD5{slash}FXSD3-Pad38)") (class "Default")
      (node (ref "U3") (pin "38") (pinfunction "FXSD5/FXSD3_38") (pintype "input"))
    )
    (net (code "90") (name "unconnected-(U3A-MDI-XDIS-Pad1)") (class "Default")
      (node (ref "U3") (pin "1") (pinfunction "MDI-XDIS_1") (pintype "input"))
    )
    (net (code "91") (name "unconnected-(U3A-MUX1-Pad45)") (class "Default")
      (node (ref "U3") (pin "45") (pinfunction "MUX1_45") (pintype "passive"))
    )
    (net (code "92") (name "unconnected-(U3A-MUX2-Pad46)") (class "Default")
      (node (ref "U3") (pin "46") (pinfunction "MUX2_46") (pintype "passive"))
    )
    (net (code "93") (name "unconnected-(U3A-PMRXC-Pad60)") (class "Default")
      (node (ref "U3") (pin "60") (pinfunction "PMRXC_60") (pintype "output"))
    )
    (net (code "94") (name "unconnected-(U3A-PMRXD1-Pad64)") (class "Default")
      (node (ref "U3") (pin "64") (pinfunction "PMRXD1_64") (pintype "bidirectional"))
    )
    (net (code "95") (name "unconnected-(U3A-PMRXD2-Pad63)") (class "Default")
      (node (ref "U3") (pin "63") (pinfunction "PMRXD2_63") (pintype "bidirectional"))
    )
    (net (code "96") (name "unconnected-(U3A-PMRXD3-Pad62)") (class "Default")
      (node (ref "U3") (pin "62") (pinfunction "PMRXD3_62") (pintype "bidirectional"))
    )
    (net (code "97") (name "unconnected-(U3A-PMRXDV-Pad61)") (class "Default")
      (node (ref "U3") (pin "61") (pinfunction "PMRXDV_61") (pintype "bidirectional"))
    )
    (net (code "98") (name "unconnected-(U3A-PMTXC-Pad57)") (class "Default")
      (node (ref "U3") (pin "57") (pinfunction "PMTXC_57") (pintype "output"))
    )
    (net (code "99") (name "unconnected-(U3A-PMTXD0-Pad55)") (class "Default")
      (node (ref "U3") (pin "55") (pinfunction "PMTXD0_55") (pintype "input"))
    )
    (net (code "100") (name "unconnected-(U3A-PMTXD1-Pad54)") (class "Default")
      (node (ref "U3") (pin "54") (pinfunction "PMTXD1_54") (pintype "input"))
    )
    (net (code "101") (name "unconnected-(U3A-PMTXD2-Pad53)") (class "Default")
      (node (ref "U3") (pin "53") (pinfunction "PMTXD2_53") (pintype "input"))
    )
    (net (code "102") (name "unconnected-(U3A-PMTXD3-Pad52)") (class "Default")
      (node (ref "U3") (pin "52") (pinfunction "PMTXD3_52") (pintype "input"))
    )
    (net (code "103") (name "unconnected-(U3A-PMTXEN-Pad51)") (class "Default")
      (node (ref "U3") (pin "51") (pinfunction "PMTXEN_51") (pintype "input"))
    )
    (net (code "104") (name "unconnected-(U3A-PMTXER-Pad56)") (class "Default")
      (node (ref "U3") (pin "56") (pinfunction "PMTXER_56") (pintype "input"))
    )
    (net (code "105") (name "unconnected-(U3A-RESERVE-Pad48)") (class "Default")
      (node (ref "U3") (pin "48") (pinfunction "RESERVE_48") (pintype "passive"))
    )
    (net (code "106") (name "unconnected-(U3B-LED1-2-Pad104)") (class "Default")
      (node (ref "U3") (pin "104") (pinfunction "LED1-2_104") (pintype "bidirectional"))
    )
    (net (code "107") (name "unconnected-(U3B-LED2-2-Pad101)") (class "Default")
      (node (ref "U3") (pin "101") (pinfunction "LED2-2_101") (pintype "bidirectional"))
    )
    (net (code "108") (name "unconnected-(U3B-LED3-2-Pad96)") (class "Default")
      (node (ref "U3") (pin "96") (pinfunction "LED3-2_96") (pintype "bidirectional"))
    )
    (net (code "109") (name "unconnected-(U3B-LED4-0-Pad95)") (class "Default")
      (node (ref "U3") (pin "95") (pinfunction "LED4-0_95") (pintype "bidirectional"))
    )
    (net (code "110") (name "unconnected-(U3B-LED4-1-Pad94)") (class "Default")
      (node (ref "U3") (pin "94") (pinfunction "LED4-1_94") (pintype "bidirectional"))
    )
    (net (code "111") (name "unconnected-(U3B-LED4-2-Pad93)") (class "Default")
      (node (ref "U3") (pin "93") (pinfunction "LED4-2_93") (pintype "bidirectional"))
    )
    (net (code "112") (name "unconnected-(U3B-LED5-0-Pad92)") (class "Default")
      (node (ref "U3") (pin "92") (pinfunction "LED5-0_92") (pintype "bidirectional"))
    )
    (net (code "113") (name "unconnected-(U3B-LED5-1-Pad91)") (class "Default")
      (node (ref "U3") (pin "91") (pinfunction "LED5-1_91") (pintype "bidirectional"))
    )
    (net (code "114") (name "unconnected-(U3B-LED5-2-Pad90)") (class "Default")
      (node (ref "U3") (pin "90") (pinfunction "LED5-2_90") (pintype "bidirectional"))
    )
    (net (code "115") (name "unconnected-(U3B-MDC-Pad107)") (class "Default")
      (node (ref "U3") (pin "107") (pinfunction "MDC_107") (pintype "input"))
    )
    (net (code "116") (name "unconnected-(U3B-MDIO-Pad108)") (class "Default")
      (node (ref "U3") (pin "108") (pinfunction "MDIO_108") (pintype "bidirectional"))
    )
    (net (code "117") (name "unconnected-(U3B-NC-Pad120)") (class "Default")
      (node (ref "U3") (pin "120") (pinfunction "NC_120") (pintype "no_connect"))
    )
    (net (code "118") (name "unconnected-(U3B-PCOL-Pad68)") (class "Default")
      (node (ref "U3") (pin "68") (pinfunction "PCOL_68") (pintype "bidirectional"))
    )
    (net (code "119") (name "unconnected-(U3B-PCRS-Pad67)") (class "Default")
      (node (ref "U3") (pin "67") (pinfunction "PCRS_67") (pintype "bidirectional"))
    )
    (net (code "120") (name "unconnected-(U3B-PMRXD0-Pad65)") (class "Default")
      (node (ref "U3") (pin "65") (pinfunction "PMRXD0_65") (pintype "bidirectional"))
    )
    (net (code "121") (name "unconnected-(U3B-PMRXER-Pad66)") (class "Default")
      (node (ref "U3") (pin "66") (pinfunction "PMRXER_66") (pintype "bidirectional"))
    )
    (net (code "122") (name "unconnected-(U3B-SCANEN-Pad119)") (class "Default")
      (node (ref "U3") (pin "119") (pinfunction "SCANEN_119") (pintype "input"))
    )
    (net (code "123") (name "unconnected-(U3B-SCOL-Pad84)") (class "Default")
      (node (ref "U3") (pin "84") (pinfunction "SCOL_84") (pintype "bidirectional"))
    )
    (net (code "124") (name "unconnected-(U3B-SCONF0-Pad87)") (class "Default")
      (node (ref "U3") (pin "87") (pinfunction "SCONF0_87") (pintype "input"))
    )
    (net (code "125") (name "unconnected-(U3B-SCONF1-Pad86)") (class "Default")
      (node (ref "U3") (pin "86") (pinfunction "SCONF1_86") (pintype "input"))
    )
    (net (code "126") (name "unconnected-(U3B-SCRS-Pad85)") (class "Default")
      (node (ref "U3") (pin "85") (pinfunction "SCRS_85") (pintype "bidirectional"))
    )
    (net (code "127") (name "unconnected-(U3B-SMRXC-Pad78)") (class "Default")
      (node (ref "U3") (pin "78") (pinfunction "SMRXC_78") (pintype "bidirectional"))
    )
    (net (code "128") (name "unconnected-(U3B-SMRXD0-Pad83)") (class "Default")
      (node (ref "U3") (pin "83") (pinfunction "SMRXD0_83") (pintype "bidirectional"))
    )
    (net (code "129") (name "unconnected-(U3B-SMRXD1-Pad82)") (class "Default")
      (node (ref "U3") (pin "82") (pinfunction "SMRXD1_82") (pintype "bidirectional"))
    )
    (net (code "130") (name "unconnected-(U3B-SMRXD2-Pad81)") (class "Default")
      (node (ref "U3") (pin "81") (pinfunction "SMRXD2_81") (pintype "bidirectional"))
    )
    (net (code "131") (name "unconnected-(U3B-SMRXD3-Pad80)") (class "Default")
      (node (ref "U3") (pin "80") (pinfunction "SMRXD3_80") (pintype "bidirectional"))
    )
    (net (code "132") (name "unconnected-(U3B-SMRXDV-Pad79)") (class "Default")
      (node (ref "U3") (pin "79") (pinfunction "SMRXDV_79") (pintype "bidirectional"))
    )
    (net (code "133") (name "unconnected-(U3B-SMTXC-Pad75)") (class "Default")
      (node (ref "U3") (pin "75") (pinfunction "SMTXC_75") (pintype "bidirectional"))
    )
    (net (code "134") (name "unconnected-(U3B-SMTXD0-Pad73)") (class "Default")
      (node (ref "U3") (pin "73") (pinfunction "SMTXD0_73") (pintype "input"))
    )
    (net (code "135") (name "unconnected-(U3B-SMTXD1-Pad72)") (class "Default")
      (node (ref "U3") (pin "72") (pinfunction "SMTXD1_72") (pintype "input"))
    )
    (net (code "136") (name "unconnected-(U3B-SMTXD2-Pad71)") (class "Default")
      (node (ref "U3") (pin "71") (pinfunction "SMTXD2_71") (pintype "input"))
    )
    (net (code "137") (name "unconnected-(U3B-SMTXD3-Pad70)") (class "Default")
      (node (ref "U3") (pin "70") (pinfunction "SMTXD3_70") (pintype "input"))
    )
    (net (code "138") (name "unconnected-(U3B-SMTXEN-Pad69)") (class "Default")
      (node (ref "U3") (pin "69") (pinfunction "SMTXEN_69") (pintype "input"))
    )
    (net (code "139") (name "unconnected-(U3B-SMTXER-Pad74)") (class "Default")
      (node (ref "U3") (pin "74") (pinfunction "SMTXER_74") (pintype "input"))
    )
    (net (code "140") (name "unconnected-(U3B-TEST2-Pad128)") (class "Default")
      (node (ref "U3") (pin "128") (pinfunction "TEST2_128") (pintype "passive"))
    )
    (net (code "141") (name "unconnected-(U3B-TESTEN-Pad118)") (class "Default")
      (node (ref "U3") (pin "118") (pinfunction "TESTEN_118") (pintype "input"))
    )
  )
)
